# Stereo_out.net
KiCad netlist of a schematic drawn in Altium Designer
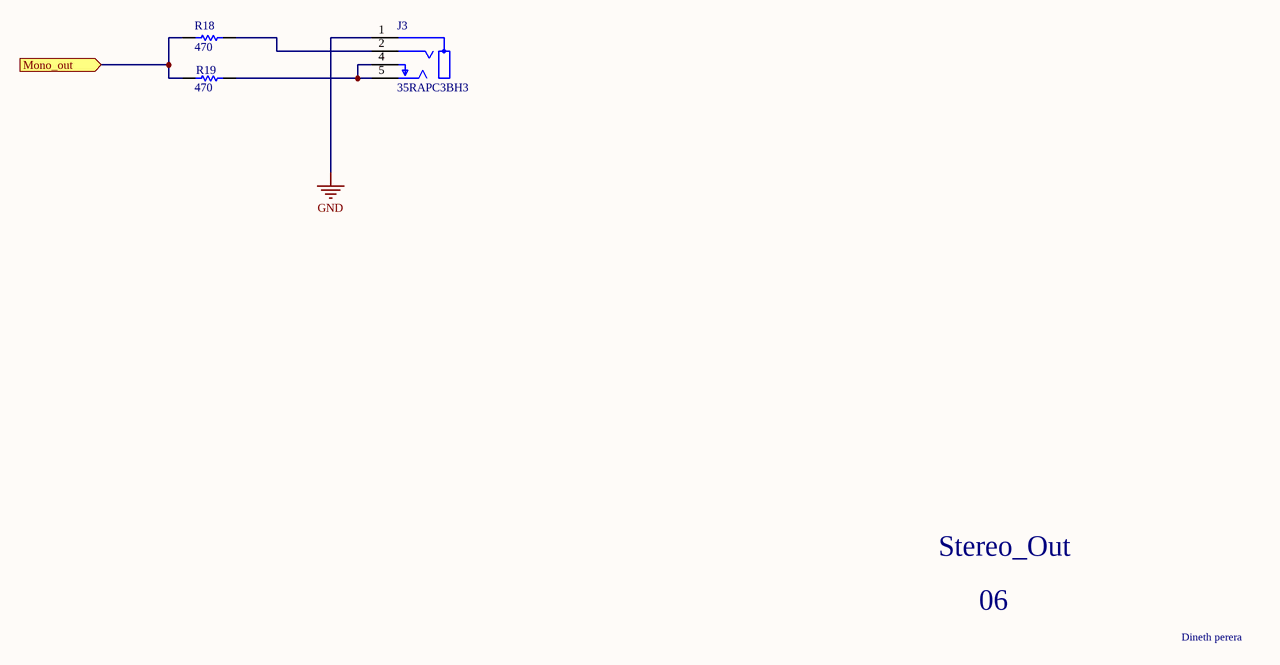
[diagram p0: Stereo_out.SchDoc]

(export (version "E")
  (design (tool "Eeschema 10.0.6"))
  (components
    (comp (ref "J3")
      (value "35RAPC3BH3")
      (footprint "FP-35RAPC3BH3-MFG")
      (description "CONN JACK STEREO 3.5MM R/A")
      (libsource (lib "Altium Content Vault") (part "6593a1246df2d7246a2ad7da18ee256"))
    )
    (comp (ref "R18")
      (value "470")
      (footprint "RESC1608X55X30ML15T15")
      (description "Chip Resistor, 470 Ohm, +/- 1%, 0.1 W, -55 to 155 degC, 0603 (1608 Metric), RoHS, Tape and Reel")
      (fields (field (name "MANUFACTURER") "Panasonic"))
      (libsource (lib "Altium Content Vault") (part "RES-2"))
    )
    (comp (ref "R19")
      (value "470")
      (footprint "RESC1608X55X30ML15T15")
      (description "Chip Resistor, 470 Ohm, +/- 1%, 0.1 W, -55 to 155 degC, 0603 (1608 Metric), RoHS, Tape and Reel")
      (fields (field (name "MANUFACTURER") "Panasonic"))
      (libsource (lib "Altium Content Vault") (part "RES-2"))
    )
  )
  (nets
    (net (code "1") (name "/Mono_out") (class "Default")
      (node (ref "R18") (pin "1") (pinfunction "1_1") (pintype "passive"))
      (node (ref "R19") (pin "1") (pinfunction "1_1") (pintype "passive"))
    )
    (net (code "2") (name "GND") (class "Default")
      (node (ref "J3") (pin "1") (pinfunction "1_1") (pintype "passive"))
    )
    (net (code "3") (name "Net-(J3-Pad2)") (class "Default")
      (node (ref "J3") (pin "2") (pinfunction "2_2") (pintype "passive"))
      (node (ref "R18") (pin "2") (pinfunction "2_2") (pintype "passive"))
    )
    (net (code "4") (name "Net-(J3-Pad4)") (class "Default")
      (node (ref "J3") (pin "4") (pinfunction "4_4") (pintype "passive"))
      (node (ref "J3") (pin "5") (pinfunction "5_5") (pintype "passive"))
      (node (ref "R19") (pin "2") (pinfunction "2_2") (pintype "passive"))
    )
  )
)
